# Drive_Board_Schematic_3_motors.net
KiCad netlist of a schematic drawn in Altium Designer
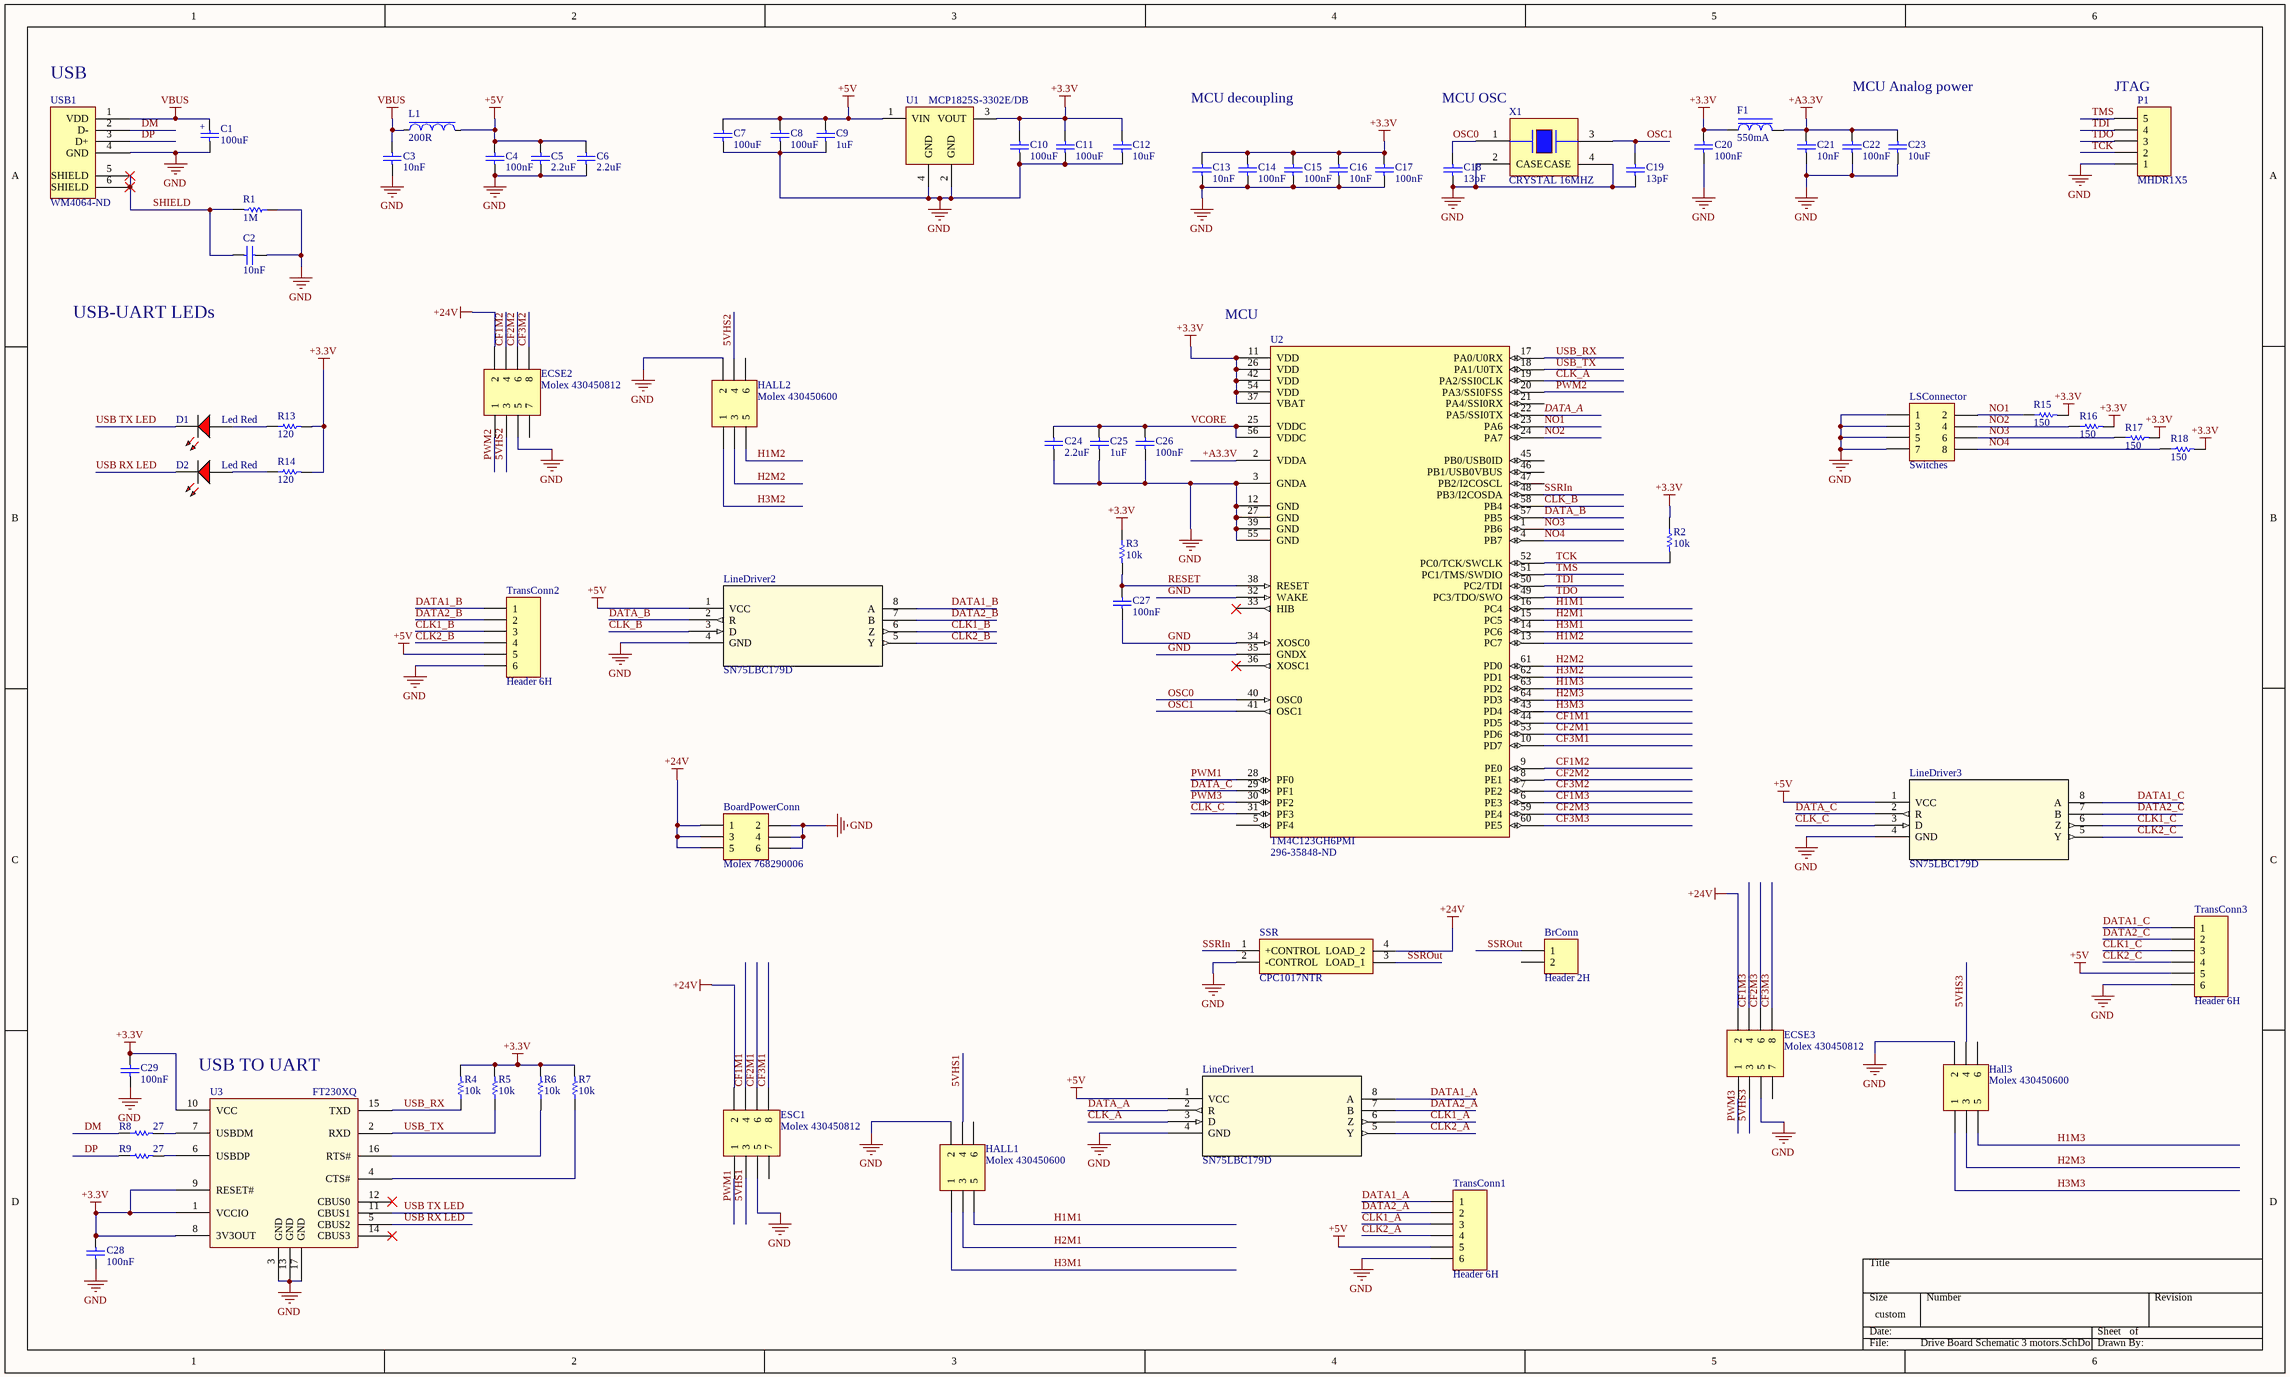
[diagram p0: Drive Board Schematic 3 motors.SchDoc]

(export (version "E")
  (design (tool "Eeschema 10.0.6"))
  (components
    (comp (ref "BoardPowerConn")
      (value "Molex 768290006")
      (footprint "HDR2X3H")
      (description "Header, 3-Pin, Dual row, Right Angle")
      (fields (field (name "PUBLISHER") "Altium Limited"))
      (libsource (lib "") (part "Header 3X2H_1"))
    )
    (comp (ref "BrConn")
      (value "Header 2H")
      (footprint "HDR1X2H")
      (description "Header, 2-Pin, Right Angle")
      (fields (field (name "PUBLISHER") "Altium Limited"))
      (libsource (lib "Miscellaneous Connectors") (part "Header 2H"))
    )
    (comp (ref "C1")
      (value "100uF")
      (footprint "CapAlu6.3mmx12.5mm")
      (description "Capacitor 35v 100uF 6.3mm")
      (fields
        (field (name "MANUFACTURER") "Nichicon")
        (field (name "MANUFACTURER PART NUMBER") "UHV1V101MED")
      )
      (libsource (lib "Capacitors") (part "100uF_35v_6.3x12.5"))
    )
    (comp (ref "C2")
      (value "10nF")
      (footprint "CAP_1206")
      (description "CAP CER 10000PF 500V X7R 1206")
      (fields
        (field (name "MANUFACTURER") "Samsung Electro-Mechanics America, Inc")
        (field (name "MANUFACTURER PART NUMBER") "CL31B103KGFNNNE")
      )
      (libsource (lib "Capacitors") (part "10nF_500V_1206"))
    )
    (comp (ref "C3")
      (value "10nF")
      (footprint "CAP_0402_M")
      (description "CAP CER 10000PF 50V 10% X7R 0402")
      (fields
        (field (name "MANUFACTURER") "Kemet")
        (field (name "MANUFACTURER PART NUMBER") "C0402C103K5RACTU")
      )
      (libsource (lib "Capacitors") (part "10nF_50V_0402"))
    )
    (comp (ref "C4")
      (value "100nF")
      (footprint "CAP_0402_M")
      (description "CAP CER 100NF 50V 20% X5R 0402")
      (fields
        (field (name "MANUFACTURER") "TDK Corporation")
        (field (name "MANUFACTURER PART NUMBER") "C1005X5R1H104M050BB")
      )
      (libsource (lib "Capacitors") (part "100nF_50V_0402"))
    )
    (comp (ref "C5")
      (value "2.2uF")
      (footprint "CAP_0402_M")
      (description "CAP CER 2.2UF 10V 20% X5R 0402")
      (fields
        (field (name "MANUFACTURER") "Taiyo Yuden")
        (field (name "MANUFACTURER PART NUMBER") "LMK105BJ225MV-F")
      )
      (libsource (lib "Capacitors") (part "2.2uF_10V_0402"))
    )
    (comp (ref "C6")
      (value "2.2uF")
      (footprint "CAP_0402_M")
      (description "CAP CER 2.2UF 10V 20% X5R 0402")
      (fields
        (field (name "MANUFACTURER") "Taiyo Yuden")
        (field (name "MANUFACTURER PART NUMBER") "LMK105BJ225MV-F")
      )
      (libsource (lib "Capacitors") (part "2.2uF_10V_0402"))
    )
    (comp (ref "C7")
      (value "100uF")
      (footprint "CAP_1206")
      (description "CAP CER 100UF 6.3V X5R 1206")
      (fields
        (field (name "MANUFACTURER") "Murata Electronics North America")
        (field (name "MANUFACTURER PART NUMBER") "GRM31CR60J107ME39L")
      )
      (libsource (lib "Capacitors") (part "100uF_6.3v_1206_X5R"))
    )
    (comp (ref "C8")
      (value "100uF")
      (footprint "CAP_1206")
      (description "CAP CER 100UF 6.3V X5R 1206")
      (fields
        (field (name "MANUFACTURER") "Murata Electronics North America")
        (field (name "MANUFACTURER PART NUMBER") "GRM31CR60J107ME39L")
      )
      (libsource (lib "Capacitors") (part "100uF_6.3v_1206_X5R"))
    )
    (comp (ref "C9")
      (value "1uF")
      (footprint "CAP_0402_M")
      (description "CAP CER 1UF 25V 10% X5R 0402")
      (fields
        (field (name "MANUFACTURER") "TDK Corporation")
        (field (name "MANUFACTURER PART NUMBER") "C1005X5R1E105K050BC")
      )
      (libsource (lib "Capacitors") (part "1uF_25V_0402"))
    )
    (comp (ref "C10")
      (value "100uF")
      (footprint "CAP_1206")
      (description "CAP CER 100UF 6.3V X5R 1206")
      (fields
        (field (name "MANUFACTURER") "Murata Electronics North America")
        (field (name "MANUFACTURER PART NUMBER") "GRM31CR60J107ME39L")
      )
      (libsource (lib "Capacitors") (part "100uF_6.3v_1206_X5R"))
    )
    (comp (ref "C11")
      (value "100uF")
      (footprint "CAP_1206")
      (description "CAP CER 100UF 6.3V X5R 1206")
      (fields
        (field (name "MANUFACTURER") "Murata Electronics North America")
        (field (name "MANUFACTURER PART NUMBER") "GRM31CR60J107ME39L")
      )
      (libsource (lib "Capacitors") (part "100uF_6.3v_1206_X5R"))
    )
    (comp (ref "C12")
      (value "10uF")
      (footprint "CAP_0603")
      (description "CAP CER 10UF 10V 20% X5R 0603")
      (fields
        (field (name "MANUFACTURER") "Taiyo Yuden")
        (field (name "MANUFACTURER PART NUMBER") "LMK107BBJ106MAHT")
      )
      (libsource (lib "Capacitors") (part "10uF_10V_0603"))
    )
    (comp (ref "C13")
      (value "10nF")
      (footprint "CAP_0402_M")
      (description "CAP CER 10000PF 50V 10% X7R 0402")
      (fields
        (field (name "MANUFACTURER") "Kemet")
        (field (name "MANUFACTURER PART NUMBER") "C0402C103K5RACTU")
      )
      (libsource (lib "Capacitors") (part "10nF_50V_0402"))
    )
    (comp (ref "C14")
      (value "100nF")
      (footprint "CAP_0402_M")
      (description "CAP CER 100NF 50V 20% X5R 0402")
      (fields
        (field (name "MANUFACTURER") "TDK Corporation")
        (field (name "MANUFACTURER PART NUMBER") "C1005X5R1H104M050BB")
      )
      (libsource (lib "Capacitors") (part "100nF_50V_0402"))
    )
    (comp (ref "C15")
      (value "100nF")
      (footprint "CAP_0402_M")
      (description "CAP CER 100NF 50V 20% X5R 0402")
      (fields
        (field (name "MANUFACTURER") "TDK Corporation")
        (field (name "MANUFACTURER PART NUMBER") "C1005X5R1H104M050BB")
      )
      (libsource (lib "Capacitors") (part "100nF_50V_0402"))
    )
    (comp (ref "C16")
      (value "10nF")
      (footprint "CAP_0402_M")
      (description "CAP CER 10000PF 50V 10% X7R 0402")
      (fields
        (field (name "MANUFACTURER") "Kemet")
        (field (name "MANUFACTURER PART NUMBER") "C0402C103K5RACTU")
      )
      (libsource (lib "Capacitors") (part "10nF_50V_0402"))
    )
    (comp (ref "C17")
      (value "100nF")
      (footprint "CAP_0402_M")
      (description "CAP CER 100NF 50V 20% X5R 0402")
      (fields
        (field (name "MANUFACTURER") "TDK Corporation")
        (field (name "MANUFACTURER PART NUMBER") "C1005X5R1H104M050BB")
      )
      (libsource (lib "Capacitors") (part "100nF_50V_0402"))
    )
    (comp (ref "C18")
      (value "13pF")
      (footprint "CAP_0402_M")
      (description "CAP CER 13PF 50V 5% NP0 0402")
      (fields
        (field (name "MANUFACTURER") "Samsung Electro-Mechanics America, Inc")
        (field (name "MANUFACTURER PART NUMBER") "CL05C130JB5NNNC")
      )
      (libsource (lib "Capacitors") (part "13pF_50V_0402"))
    )
    (comp (ref "C19")
      (value "13pF")
      (footprint "CAP_0402_M")
      (description "CAP CER 13PF 50V 5% NP0 0402")
      (fields
        (field (name "MANUFACTURER") "Samsung Electro-Mechanics America, Inc")
        (field (name "MANUFACTURER PART NUMBER") "CL05C130JB5NNNC")
      )
      (libsource (lib "Capacitors") (part "13pF_50V_0402"))
    )
    (comp (ref "C20")
      (value "100nF")
      (footprint "CAP_0402_M")
      (description "CAP CER 100NF 50V 20% X5R 0402")
      (fields
        (field (name "MANUFACTURER") "TDK Corporation")
        (field (name "MANUFACTURER PART NUMBER") "C1005X5R1H104M050BB")
      )
      (libsource (lib "Capacitors") (part "100nF_50V_0402"))
    )
    (comp (ref "C21")
      (value "10nF")
      (footprint "CAP_0402_M")
      (description "CAP CER 10000PF 50V 10% X7R 0402")
      (fields
        (field (name "MANUFACTURER") "Kemet")
        (field (name "MANUFACTURER PART NUMBER") "C0402C103K5RACTU")
      )
      (libsource (lib "Capacitors") (part "10nF_50V_0402"))
    )
    (comp (ref "C22")
      (value "100nF")
      (footprint "CAP_0402_M")
      (description "CAP CER 100NF 50V 20% X5R 0402")
      (fields
        (field (name "MANUFACTURER") "TDK Corporation")
        (field (name "MANUFACTURER PART NUMBER") "C1005X5R1H104M050BB")
      )
      (libsource (lib "Capacitors") (part "100nF_50V_0402"))
    )
    (comp (ref "C23")
      (value "10uF")
      (footprint "CAP_0603")
      (description "CAP CER 10UF 10V 20% X5R 0603")
      (fields
        (field (name "MANUFACTURER") "Taiyo Yuden")
        (field (name "MANUFACTURER PART NUMBER") "LMK107BBJ106MAHT")
      )
      (libsource (lib "Capacitors") (part "10uF_10V_0603"))
    )
    (comp (ref "C24")
      (value "2.2uF")
      (footprint "CAP_0603")
      (description "CAP CER 2.2UF 35V 10% X5R 0603")
      (fields
        (field (name "MANUFACTURER") "Murata Electronics North America")
        (field (name "MANUFACTURER PART NUMBER") "GRM188R6YA225KA12D")
      )
      (libsource (lib "Capacitors") (part "2.2uF_35V_0603"))
    )
    (comp (ref "C25")
      (value "1uF")
      (footprint "CAP_0402_M")
      (description "CAP CER 1UF 25V 10% X5R 0402")
      (fields
        (field (name "MANUFACTURER") "TDK Corporation")
        (field (name "MANUFACTURER PART NUMBER") "C1005X5R1E105K050BC")
      )
      (libsource (lib "Capacitors") (part "1uF_25V_0402"))
    )
    (comp (ref "C26")
      (value "100nF")
      (footprint "CAP_0402_M")
      (description "CAP CER 100NF 50V 20% X5R 0402")
      (fields
        (field (name "MANUFACTURER") "TDK Corporation")
        (field (name "MANUFACTURER PART NUMBER") "C1005X5R1H104M050BB")
      )
      (libsource (lib "Capacitors") (part "100nF_50V_0402"))
    )
    (comp (ref "C27")
      (value "100nF")
      (footprint "CAP_0402_M")
      (description "CAP CER 100NF 50V 20% X5R 0402")
      (fields
        (field (name "MANUFACTURER") "TDK Corporation")
        (field (name "MANUFACTURER PART NUMBER") "C1005X5R1H104M050BB")
      )
      (libsource (lib "Capacitors") (part "100nF_50V_0402"))
    )
    (comp (ref "C28")
      (value "100nF")
      (footprint "CAP_0402_M")
      (description "CAP CER 100NF 50V 20% X5R 0402")
      (fields
        (field (name "MANUFACTURER") "TDK Corporation")
        (field (name "MANUFACTURER PART NUMBER") "C1005X5R1H104M050BB")
      )
      (libsource (lib "Capacitors") (part "100nF_50V_0402"))
    )
    (comp (ref "C29")
      (value "100nF")
      (footprint "CAP_0402_M")
      (description "CAP CER 100NF 50V 20% X5R 0402")
      (fields
        (field (name "MANUFACTURER") "TDK Corporation")
        (field (name "MANUFACTURER PART NUMBER") "C1005X5R1H104M050BB")
      )
      (libsource (lib "Capacitors") (part "100nF_50V_0402"))
    )
    (comp (ref "D1")
      (value "Led Red")
      (footprint "TOPLED 0805")
      (description "LED TOPLED 630NM SUP RED CLR SMD")
      (fields
        (field (name "MANUFACTURER") "OSRAM Opto Semiconductors Inc")
        (field (name "MANUFACTURER PART NUMBER") "LS M67K-H2L1-1-Z")
      )
      (libsource (lib "Diodes") (part "TOPLED 0803"))
    )
    (comp (ref "D2")
      (value "Led Red")
      (footprint "TOPLED 0805")
      (description "LED TOPLED 630NM SUP RED CLR SMD")
      (fields
        (field (name "MANUFACTURER") "OSRAM Opto Semiconductors Inc")
        (field (name "MANUFACTURER PART NUMBER") "LS M67K-H2L1-1-Z")
      )
      (libsource (lib "Diodes") (part "TOPLED 0803"))
    )
    (comp (ref "ECSE2")
      (value "Molex 430450812")
      (footprint "HDR2X4H")
      (description "Header, 4-Pin, Dual row, Right Angle")
      (fields (field (name "PUBLISHER") "Altium Limited"))
      (libsource (lib "Miscellaneous Connectors") (part "Header 4X2H"))
    )
    (comp (ref "ECSE3")
      (value "Molex 430450812")
      (footprint "HDR2X4H")
      (description "Header, 4-Pin, Dual row, Right Angle")
      (fields (field (name "PUBLISHER") "Altium Limited"))
      (libsource (lib "Miscellaneous Connectors") (part "Header 4X2H"))
    )
    (comp (ref "ESC1")
      (value "Molex 430450812")
      (footprint "HDR2X4H")
      (description "Header, 4-Pin, Dual row, Right Angle")
      (fields (field (name "PUBLISHER") "Altium Limited"))
      (libsource (lib "Miscellaneous Connectors") (part "Header 4X2H"))
    )
    (comp (ref "F1")
      (value "550mA")
      (footprint "RES_0402_M")
      (description "FERRITE CHIP 40 OHM 550MA 0402")
      (fields
        (field (name "MANUFACTURER") "TDK Corporation")
        (field (name "MANUFACTURER PART NUMBER") "MMZ1005Y400CT000")
      )
      (libsource (lib "Resistors") (part "40O_550mA_0402"))
    )
    (comp (ref "HALL1")
      (value "Molex 430450600")
      (footprint "HDR2X3H")
      (description "Header, 3-Pin, Dual row, Right Angle")
      (fields (field (name "PUBLISHER") "Altium Limited"))
      (libsource (lib "Miscellaneous Connectors") (part "Header 3X2H"))
    )
    (comp (ref "HALL2")
      (value "Molex 430450600")
      (footprint "HDR2X3H")
      (description "Header, 3-Pin, Dual row, Right Angle")
      (fields (field (name "PUBLISHER") "Altium Limited"))
      (libsource (lib "Miscellaneous Connectors") (part "Header 3X2H"))
    )
    (comp (ref "Hall3")
      (value "Molex 430450600")
      (footprint "HDR2X3H")
      (description "Header, 3-Pin, Dual row, Right Angle")
      (fields (field (name "PUBLISHER") "Altium Limited"))
      (libsource (lib "Miscellaneous Connectors") (part "Header 3X2H"))
    )
    (comp (ref "L1")
      (value "200R")
      (footprint "IND_0603")
      (description "FILTER CHIP 220 OHM 2A 0603")
      (fields
        (field (name "MANUFACTURER") "Murata Electronics North America")
        (field (name "MANUFACTURER PART NUMBER") "BLM18EG221SN1D")
      )
      (libsource (lib "Inductors") (part "Ferrite_200 ohms_2A"))
    )
    (comp (ref "LineDriver1")
      (value "SN75LBC179D")
      (footprint "D8")
      (description "Low-Power Differential Line Driver And Receiver Pair")
      (fields
        (field (name "MANUFACTURER") "Texas Instruments")
        (field (name "GENERIC_PART_NUMBER") "SN75LBC179")
        (field (name "COPYRIGHT") "Copyright (C) 2018 Accelerated Designs. All rights reserved")
      )
      (libsource (lib "2020-08-25_19-06-54") (part "SN75LBC179D"))
    )
    (comp (ref "LineDriver2")
      (value "SN75LBC179D")
      (footprint "D8")
      (description "Low-Power Differential Line Driver And Receiver Pair")
      (fields
        (field (name "MANUFACTURER") "Texas Instruments")
        (field (name "GENERIC_PART_NUMBER") "SN75LBC179")
        (field (name "COPYRIGHT") "Copyright (C) 2018 Accelerated Designs. All rights reserved")
      )
      (libsource (lib "2020-08-25_19-06-54") (part "SN75LBC179D"))
    )
    (comp (ref "LineDriver3")
      (value "SN75LBC179D")
      (footprint "D8")
      (description "Low-Power Differential Line Driver And Receiver Pair")
      (fields
        (field (name "MANUFACTURER") "Texas Instruments")
        (field (name "GENERIC_PART_NUMBER") "SN75LBC179")
        (field (name "COPYRIGHT") "Copyright (C) 2018 Accelerated Designs. All rights reserved")
      )
      (libsource (lib "2020-08-25_19-06-54") (part "SN75LBC179D"))
    )
    (comp (ref "LSConnector")
      (value "Switches")
      (footprint "MHDR2X4")
      (description "Header, 4-Pin, Dual row")
      (fields (field (name "PUBLISHER") "Altium Limited"))
      (libsource (lib "Miscellaneous Connectors") (part "MHDR2X4"))
    )
    (comp (ref "P1")
      (value "MHDR1X5")
      (footprint "MHDR1X5")
      (description "Header, 5-Pin")
      (fields (field (name "PUBLISHER") "Altium Limited"))
      (libsource (lib "Miscellaneous Connectors") (part "MHDR1X5"))
    )
    (comp (ref "R1")
      (value "1M")
      (footprint "RES_1206")
      (description "RES SMD 1M OHM 5% 1/4W 1206")
      (fields
        (field (name "MANUFACTURER") "Panasonic Electronic Components")
        (field (name "MANUFACTURER PART NUMBER") "ERJ-8GEYJ105V")
      )
      (libsource (lib "Resistors") (part "1M_5%_1206"))
    )
    (comp (ref "R2")
      (value "10k")
      (footprint "RES_0402_M")
      (description "RES SMD 10K OHM 1% 1/10W 0402")
      (fields
        (field (name "MANUFACTURER") "Panasonic Electronic Components")
        (field (name "MANUFACTURER PART NUMBER") "ERJ-2RKF1002X")
      )
      (libsource (lib "Resistors") (part "10k_1%_0402"))
    )
    (comp (ref "R3")
      (value "10k")
      (footprint "RES_0402_M")
      (description "RES SMD 10K OHM 1% 1/10W 0402")
      (fields
        (field (name "MANUFACTURER") "Panasonic Electronic Components")
        (field (name "MANUFACTURER PART NUMBER") "ERJ-2RKF1002X")
      )
      (libsource (lib "Resistors") (part "10k_1%_0402"))
    )
    (comp (ref "R4")
      (value "10k")
      (footprint "RES_0402_M")
      (description "RES SMD 10K OHM 1% 1/10W 0402")
      (fields
        (field (name "MANUFACTURER") "Panasonic Electronic Components")
        (field (name "MANUFACTURER PART NUMBER") "ERJ-2RKF1002X")
      )
      (libsource (lib "Resistors") (part "10k_1%_0402"))
    )
    (comp (ref "R5")
      (value "10k")
      (footprint "RES_0402_M")
      (description "RES SMD 10K OHM 1% 1/10W 0402")
      (fields
        (field (name "MANUFACTURER") "Panasonic Electronic Components")
        (field (name "MANUFACTURER PART NUMBER") "ERJ-2RKF1002X")
      )
      (libsource (lib "Resistors") (part "10k_1%_0402"))
    )
    (comp (ref "R6")
      (value "10k")
      (footprint "RES_0402_M")
      (description "RES SMD 10K OHM 1% 1/10W 0402")
      (fields
        (field (name "MANUFACTURER") "Panasonic Electronic Components")
        (field (name "MANUFACTURER PART NUMBER") "ERJ-2RKF1002X")
      )
      (libsource (lib "Resistors") (part "10k_1%_0402"))
    )
    (comp (ref "R7")
      (value "10k")
      (footprint "RES_0402_M")
      (description "RES SMD 10K OHM 1% 1/10W 0402")
      (fields
        (field (name "MANUFACTURER") "Panasonic Electronic Components")
        (field (name "MANUFACTURER PART NUMBER") "ERJ-2RKF1002X")
      )
      (libsource (lib "Resistors") (part "10k_1%_0402"))
    )
    (comp (ref "R8")
      (value "27")
      (footprint "RES_0402_M")
      (description "RES SMD 27 OHM 1% 1/10W 0402")
      (fields
        (field (name "MANUFACTURER") "Panasonic Electronic Components")
        (field (name "MANUFACTURER PART NUMBER") "ERJ-2RKF27R0X")
      )
      (libsource (lib "Resistors") (part "27_1%_0402"))
    )
    (comp (ref "R9")
      (value "27")
      (footprint "RES_0402_M")
      (description "RES SMD 27 OHM 1% 1/10W 0402")
      (fields
        (field (name "MANUFACTURER") "Panasonic Electronic Components")
        (field (name "MANUFACTURER PART NUMBER") "ERJ-2RKF27R0X")
      )
      (libsource (lib "Resistors") (part "27_1%_0402"))
    )
    (comp (ref "R13")
      (value "120")
      (footprint "RES_0402_M")
      (description "RES SMD 120 OHM 1% 1/10W 0402")
      (fields
        (field (name "MANUFACTURER") "Panasonic Electronic Components")
        (field (name "MANUFACTURER PART NUMBER") "ERJ-2RKF1200X")
      )
      (libsource (lib "Resistors") (part "120_1%_0402"))
    )
    (comp (ref "R14")
      (value "120")
      (footprint "RES_0402_M")
      (description "RES SMD 120 OHM 1% 1/10W 0402")
      (fields
        (field (name "MANUFACTURER") "Panasonic Electronic Components")
        (field (name "MANUFACTURER PART NUMBER") "ERJ-2RKF1200X")
      )
      (libsource (lib "Resistors") (part "120_1%_0402"))
    )
    (comp (ref "R15")
      (value "150")
      (footprint "RES_0402_M")
      (description "RES SMD 10K OHM 1% 1/10W 0402")
      (fields
        (field (name "MANUFACTURER") "Panasonic Electronic Components")
        (field (name "MANUFACTURER PART NUMBER") "ERJ-2RKF1002X")
      )
      (libsource (lib "Resistors") (part "10k_1%_0402"))
    )
    (comp (ref "R16")
      (value "150")
      (footprint "RES_0402_M")
      (description "RES SMD 10K OHM 1% 1/10W 0402")
      (fields
        (field (name "MANUFACTURER") "Panasonic Electronic Components")
        (field (name "MANUFACTURER PART NUMBER") "ERJ-2RKF1002X")
      )
      (libsource (lib "Resistors") (part "10k_1%_0402"))
    )
    (comp (ref "R17")
      (value "150")
      (footprint "RES_0402_M")
      (description "RES SMD 10K OHM 1% 1/10W 0402")
      (fields
        (field (name "MANUFACTURER") "Panasonic Electronic Components")
        (field (name "MANUFACTURER PART NUMBER") "ERJ-2RKF1002X")
      )
      (libsource (lib "Resistors") (part "10k_1%_0402"))
    )
    (comp (ref "R18")
      (value "150")
      (footprint "RES_0402_M")
      (description "RES SMD 10K OHM 1% 1/10W 0402")
      (fields
        (field (name "MANUFACTURER") "Panasonic Electronic Components")
        (field (name "MANUFACTURER PART NUMBER") "ERJ-2RKF1002X")
      )
      (libsource (lib "Resistors") (part "10k_1%_0402"))
    )
    (comp (ref "SSR")
      (value "CPC1017NTR")
      (footprint "SamacSys:SOP254P610X216-4N")
      (description "Relay or Contactor")
      (fields (field (name "MOUSER PART NUMBER") "849-CPC1017NTR"))
      (libsource (lib "*") (part "CPC1017NTR"))
    )
    (comp (ref "TransConn1")
      (value "Header 6H")
      (footprint "HDR1X6H")
      (description "Header, 6-Pin, Right Angle")
      (fields (field (name "PUBLISHER") "Altium Limited"))
      (libsource (lib "Miscellaneous Connectors") (part "Header 6H"))
    )
    (comp (ref "TransConn2")
      (value "Header 6H")
      (footprint "HDR1X6H")
      (description "Header, 6-Pin, Right Angle")
      (fields (field (name "PUBLISHER") "Altium Limited"))
      (libsource (lib "Miscellaneous Connectors") (part "Header 6H"))
    )
    (comp (ref "TransConn3")
      (value "Header 6H")
      (footprint "HDR1X6H")
      (description "Header, 6-Pin, Right Angle")
      (fields (field (name "PUBLISHER") "Altium Limited"))
      (libsource (lib "Miscellaneous Connectors") (part "Header 6H"))
    )
    (comp (ref "U1")
      (value "MCP1825S-3302E/DB")
      (footprint "SOT230P700X180-4N")
      (description "500 mA, Low Voltage, Low Quiescent Current LDO Regulator")
      (fields (field (name "MANUFACTURER") "Microchip Technology"))
      (libsource (lib "ICs") (part "MCP1825S-3302E/DB"))
    )
    (comp (ref "U2")
      (value "TM4C123GH6PMI")
      (footprint "TSQFP50P1200X1200X120-64N")
      (description "Tiva TM4C123GH6PM Microcontroller ARM Cortex 80 MHz FPU")
      (fields (field (name "SUPPLIER PART NUMBER 1") "296-35848-ND"))
      (libsource (lib "ICs") (part "TM4C123GH6PMI"))
    )
    (comp (ref "U3")
      (value "FT230XQ")
      (footprint "QFN65P400X400X80_HS-17N")
      (description "IC USB SERIAL BASIC UART 16QFN")
      (fields
        (field (name "MANUFACTURER") "FTDI, Future Technology Devices International Ltd")
        (field (name "MANUFACTURER PART NUMBER") "FT230XQ-R")
      )
      (libsource (lib "ICs") (part "FT230XQ-R"))
    )
    (comp (ref "USB1")
      (value "USB type-B jack")
      (footprint "USB2.5-2H4E")
      (fields (field (name "SUPPLIER PART NUMBER 1") "WM4064-ND"))
      (libsource (lib "Connectors") (part "MOLEX 0670688010"))
    )
    (comp (ref "X1")
      (value "CRYSTAL 16MHZ")
      (footprint "CRYSTAL_3.2x2.5")
      (description "CRYSTAL 16MHZ 20PF SMD")
      (fields
        (field (name "MANUFACTURER") "CTS-Frequency Controls")
        (field (name "MANUFACTURER PART NUMBER") "403C35E16M00000")
      )
      (libsource (lib "ICs") (part "403C35E16M00000"))
    )
  )
  (nets
    (net (code "1") (name "+3.3V") (class "Default")
      (node (ref "C10") (pin "1") (pinfunction "1_1") (pintype "passive"))
      (node (ref "C11") (pin "1") (pinfunction "1_1") (pintype "passive"))
      (node (ref "C12") (pin "1") (pinfunction "1_1") (pintype "passive"))
      (node (ref "C13") (pin "2") (pinfunction "2_2") (pintype "passive"))
      (node (ref "C14") (pin "2") (pinfunction "2_2") (pintype "passive"))
      (node (ref "C15") (pin "2") (pinfunction "2_2") (pintype "passive"))
      (node (ref "C16") (pin "2") (pinfunction "2_2") (pintype "passive"))
      (node (ref "C17") (pin "2") (pinfunction "2_2") (pintype "passive"))
      (node (ref "C20") (pin "2") (pinfunction "2_2") (pintype "passive"))
      (node (ref "C28") (pin "2") (pinfunction "2_2") (pintype "passive"))
      (node (ref "C29") (pin "2") (pinfunction "2_2") (pintype "passive"))
      (node (ref "F1") (pin "1") (pinfunction "1_1") (pintype "passive"))
      (node (ref "R13") (pin "2") (pinfunction "2_2") (pintype "passive"))
      (node (ref "R14") (pin "2") (pinfunction "2_2") (pintype "passive"))
      (node (ref "R15") (pin "2") (pinfunction "2_2") (pintype "passive"))
      (node (ref "R16") (pin "2") (pinfunction "2_2") (pintype "passive"))
      (node (ref "R17") (pin "2") (pinfunction "2_2") (pintype "passive"))
      (node (ref "R18") (pin "2") (pinfunction "2_2") (pintype "passive"))
      (node (ref "R2") (pin "1") (pinfunction "1_1") (pintype "passive"))
      (node (ref "R3") (pin "1") (pinfunction "1_1") (pintype "passive"))
      (node (ref "R4") (pin "2") (pinfunction "2_2") (pintype "passive"))
      (node (ref "R5") (pin "2") (pinfunction "2_2") (pintype "passive"))
      (node (ref "R6") (pin "2") (pinfunction "2_2") (pintype "passive"))
      (node (ref "R7") (pin "2") (pinfunction "2_2") (pintype "passive"))
      (node (ref "U1") (pin "3") (pinfunction "VOUT_3") (pintype "power_in"))
      (node (ref "U2") (pin "11") (pinfunction "VDD_11") (pintype "power_in"))
      (node (ref "U2") (pin "26") (pinfunction "VDD_26") (pintype "power_in"))
      (node (ref "U2") (pin "37") (pinfunction "VBAT_37") (pintype "power_in"))
      (node (ref "U2") (pin "42") (pinfunction "VDD_42") (pintype "power_in"))
      (node (ref "U2") (pin "54") (pinfunction "VDD_54") (pintype "power_in"))
      (node (ref "U3") (pin "1") (pinfunction "VCCIO_1") (pintype "passive"))
      (node (ref "U3") (pin "10") (pinfunction "VCC_10") (pintype "passive"))
      (node (ref "U3") (pin "8") (pinfunction "3V3OUT_8") (pintype "passive"))
      (node (ref "U3") (pin "9") (pinfunction "RESET#_9") (pintype "passive"))
    )
    (net (code "2") (name "+5V") (class "Default")
      (node (ref "C4") (pin "2") (pinfunction "2_2") (pintype "passive"))
      (node (ref "C5") (pin "2") (pinfunction "2_2") (pintype "passive"))
      (node (ref "C6") (pin "2") (pinfunction "2_2") (pintype "passive"))
      (node (ref "C7") (pin "1") (pinfunction "1_1") (pintype "passive"))
      (node (ref "C8") (pin "1") (pinfunction "1_1") (pintype "passive"))
      (node (ref "C9") (pin "2") (pinfunction "2_2") (pintype "passive"))
      (node (ref "L1") (pin "2") (pinfunction "2_2") (pintype "passive"))
      (node (ref "LineDriver1") (pin "1") (pinfunction "VCC_1") (pintype "power_in"))
      (node (ref "LineDriver2") (pin "1") (pinfunction "VCC_1") (pintype "power_in"))
      (node (ref "LineDriver3") (pin "1") (pinfunction "VCC_1") (pintype "power_in"))
      (node (ref "TransConn1") (pin "5") (pinfunction "5_5") (pintype "passive"))
      (node (ref "TransConn2") (pin "5") (pinfunction "5_5") (pintype "passive"))
      (node (ref "TransConn3") (pin "5") (pinfunction "5_5") (pintype "passive"))
      (node (ref "U1") (pin "1") (pinfunction "VIN_1") (pintype "power_in"))
    )
    (net (code "3") (name "+24V") (class "Default")
      (node (ref "BoardPowerConn") (pin "1") (pinfunction "1_1") (pintype "passive"))
      (node (ref "BoardPowerConn") (pin "3") (pinfunction "3_3") (pintype "passive"))
      (node (ref "BoardPowerConn") (pin "5") (pinfunction "5_5") (pintype "passive"))
      (node (ref "ECSE2") (pin "2") (pinfunction "2_2") (pintype "passive"))
      (node (ref "ECSE3") (pin "2") (pinfunction "2_2") (pintype "passive"))
      (node (ref "ESC1") (pin "2") (pinfunction "2_2") (pintype "passive"))
      (node (ref "SSR") (pin "4") (pinfunction "LOAD_2_4") (pintype "passive"))
    )
    (net (code "4") (name "+A3.3V") (class "Default")
      (node (ref "C21") (pin "2") (pinfunction "2_2") (pintype "passive"))
      (node (ref "C22") (pin "2") (pinfunction "2_2") (pintype "passive"))
      (node (ref "C23") (pin "2") (pinfunction "2_2") (pintype "passive"))
      (node (ref "F1") (pin "2") (pinfunction "2_2") (pintype "passive"))
      (node (ref "U2") (pin "2") (pinfunction "VDDA_2") (pintype "power_in"))
    )
    (net (code "5") (name "/5VHS1") (class "Default")
      (node (ref "ESC1") (pin "3") (pinfunction "3_3") (pintype "passive"))
      (node (ref "HALL1") (pin "4") (pinfunction "4_4") (pintype "passive"))
    )
    (net (code "6") (name "/5VHS2") (class "Default")
      (node (ref "ECSE2") (pin "3") (pinfunction "3_3") (pintype "passive"))
      (node (ref "HALL2") (pin "4") (pinfunction "4_4") (pintype "passive"))
    )
    (net (code "7") (name "/5VHS3") (class "Default")
      (node (ref "ECSE3") (pin "3") (pinfunction "3_3") (pintype "passive"))
      (node (ref "Hall3") (pin "4") (pinfunction "4_4") (pintype "passive"))
    )
    (net (code "8") (name "/CF1M1") (class "Default")
      (node (ref "ESC1") (pin "4") (pinfunction "4_4") (pintype "passive"))
      (node (ref "U2") (pin "44") (pinfunction "PD5_44") (pintype "bidirectional"))
    )
    (net (code "9") (name "/CF1M2") (class "Default")
      (node (ref "ECSE2") (pin "4") (pinfunction "4_4") (pintype "passive"))
      (node (ref "U2") (pin "9") (pinfunction "PE0_9") (pintype "bidirectional"))
    )
    (net (code "10") (name "/CF1M3") (class "Default")
      (node (ref "ECSE3") (pin "4") (pinfunction "4_4") (pintype "passive"))
      (node (ref "U2") (pin "6") (pinfunction "PE3_6") (pintype "bidirectional"))
    )
    (net (code "11") (name "/CF2M1") (class "Default")
      (node (ref "ESC1") (pin "6") (pinfunction "6_6") (pintype "passive"))
      (node (ref "U2") (pin "53") (pinfunction "PD6_53") (pintype "bidirectional"))
    )
    (net (code "12") (name "/CF2M2") (class "Default")
      (node (ref "ECSE2") (pin "6") (pinfunction "6_6") (pintype "passive"))
      (node (ref "U2") (pin "8") (pinfunction "PE1_8") (pintype "bidirectional"))
    )
    (net (code "13") (name "/CF2M3") (class "Default")
      (node (ref "ECSE3") (pin "6") (pinfunction "6_6") (pintype "passive"))
      (node (ref "U2") (pin "59") (pinfunction "PE4_59") (pintype "bidirectional"))
    )
    (net (code "14") (name "/CF3M1") (class "Default")
      (node (ref "ESC1") (pin "8") (pinfunction "8_8") (pintype "passive"))
      (node (ref "U2") (pin "10") (pinfunction "PD7_10") (pintype "bidirectional"))
    )
    (net (code "15") (name "/CF3M2") (class "Default")
      (node (ref "ECSE2") (pin "8") (pinfunction "8_8") (pintype "passive"))
      (node (ref "U2") (pin "7") (pinfunction "PE2_7") (pintype "bidirectional"))
    )
    (net (code "16") (name "/CF3M3") (class "Default")
      (node (ref "ECSE3") (pin "8") (pinfunction "8_8") (pintype "passive"))
      (node (ref "U2") (pin "60") (pinfunction "PE5_60") (pintype "bidirectional"))
    )
    (net (code "17") (name "/CLK1_A") (class "Default")
      (node (ref "LineDriver1") (pin "6") (pinfunction "Z_6") (pintype "output"))
      (node (ref "TransConn1") (pin "3") (pinfunction "3_3") (pintype "passive"))
    )
    (net (code "18") (name "/CLK1_B") (class "Default")
      (node (ref "LineDriver2") (pin "6") (pinfunction "Z_6") (pintype "output"))
      (node (ref "TransConn2") (pin "3") (pinfunction "3_3") (pintype "passive"))
    )
    (net (code "19") (name "/CLK1_C") (class "Default")
      (node (ref "LineDriver3") (pin "6") (pinfunction "Z_6") (pintype "output"))
      (node (ref "TransConn3") (pin "3") (pinfunction "3_3") (pintype "passive"))
    )
    (net (code "20") (name "/CLK2_A") (class "Default")
      (node (ref "LineDriver1") (pin "5") (pinfunction "Y_5") (pintype "output"))
      (node (ref "TransConn1") (pin "4") (pinfunction "4_4") (pintype "passive"))
    )
    (net (code "21") (name "/CLK2_B") (class "Default")
      (node (ref "LineDriver2") (pin "5") (pinfunction "Y_5") (pintype "output"))
      (node (ref "TransConn2") (pin "4") (pinfunction "4_4") (pintype "passive"))
    )
    (net (code "22") (name "/CLK2_C") (class "Default")
      (node (ref "LineDriver3") (pin "5") (pinfunction "Y_5") (pintype "output"))
      (node (ref "TransConn3") (pin "4") (pinfunction "4_4") (pintype "passive"))
    )
    (net (code "23") (name "/CLK_A") (class "Default")
      (node (ref "LineDriver1") (pin "3") (pinfunction "D_3") (pintype "input"))
      (node (ref "U2") (pin "19") (pinfunction "PA2/SSI0CLK_19") (pintype "bidirectional"))
    )
    (net (code "24") (name "/CLK_B") (class "Default")
      (node (ref "LineDriver2") (pin "3") (pinfunction "D_3") (pintype "input"))
      (node (ref "U2") (pin "58") (pinfunction "PB4_58") (pintype "bidirectional"))
    )
    (net (code "25") (name "/CLK_C") (class "Default")
      (node (ref "LineDriver3") (pin "3") (pinfunction "D_3") (pintype "input"))
      (node (ref "U2") (pin "31") (pinfunction "PF3_31") (pintype "bidirectional"))
    )
    (net (code "26") (name "/DATA1_A") (class "Default")
      (node (ref "LineDriver1") (pin "8") (pinfunction "A_8") (pintype "passive"))
      (node (ref "TransConn1") (pin "1") (pinfunction "1_1") (pintype "passive"))
    )
    (net (code "27") (name "/DATA1_B") (class "Default")
      (node (ref "LineDriver2") (pin "8") (pinfunction "A_8") (pintype "passive"))
      (node (ref "TransConn2") (pin "1") (pinfunction "1_1") (pintype "passive"))
    )
    (net (code "28") (name "/DATA1_C") (class "Default")
      (node (ref "LineDriver3") (pin "8") (pinfunction "A_8") (pintype "passive"))
      (node (ref "TransConn3") (pin "1") (pinfunction "1_1") (pintype "passive"))
    )
    (net (code "29") (name "/DATA2_A") (class "Default")
      (node (ref "LineDriver1") (pin "7") (pinfunction "B_7") (pintype "passive"))
      (node (ref "TransConn1") (pin "2") (pinfunction "2_2") (pintype "passive"))
    )
    (net (code "30") (name "/DATA2_B") (class "Default")
      (node (ref "LineDriver2") (pin "7") (pinfunction "B_7") (pintype "passive"))
      (node (ref "TransConn2") (pin "2") (pinfunction "2_2") (pintype "passive"))
    )
    (net (code "31") (name "/DATA2_C") (class "Default")
      (node (ref "LineDriver3") (pin "7") (pinfunction "B_7") (pintype "passive"))
      (node (ref "TransConn3") (pin "2") (pinfunction "2_2") (pintype "passive"))
    )
    (net (code "32") (name "/DATA_A") (class "Default")
      (node (ref "LineDriver1") (pin "2") (pinfunction "R_2") (pintype "output"))
      (node (ref "U2") (pin "22") (pinfunction "PA5/SSI0TX_22") (pintype "bidirectional"))
    )
    (net (code "33") (name "/DATA_B") (class "Default")
      (node (ref "LineDriver2") (pin "2") (pinfunction "R_2") (pintype "output"))
      (node (ref "U2") (pin "57") (pinfunction "PB5_57") (pintype "bidirectional"))
    )
    (net (code "34") (name "/DATA_C") (class "Default")
      (node (ref "LineDriver3") (pin "2") (pinfunction "R_2") (pintype "output"))
      (node (ref "U2") (pin "29") (pinfunction "PF1_29") (pintype "bidirectional"))
    )
    (net (code "35") (name "/DM") (class "Default")
      (node (ref "R8") (pin "1") (pinfunction "1_1") (pintype "passive"))
      (node (ref "USB1") (pin "2") (pinfunction "D-_2") (pintype "passive"))
    )
    (net (code "36") (name "/DP") (class "Default")
      (node (ref "R9") (pin "1") (pinfunction "1_1") (pintype "passive"))
      (node (ref "USB1") (pin "3") (pinfunction "D+_3") (pintype "passive"))
    )
    (net (code "37") (name "/H1M1") (class "Default")
      (node (ref "HALL1") (pin "5") (pinfunction "5_5") (pintype "passive"))
      (node (ref "U2") (pin "16") (pinfunction "PC4_16") (pintype "bidirectional"))
    )
    (net (code "38") (name "/H1M2") (class "Default")
      (node (ref "HALL2") (pin "5") (pinfunction "5_5") (pintype "passive"))
      (node (ref "U2") (pin "13") (pinfunction "PC7_13") (pintype "bidirectional"))
    )
    (net (code "39") (name "/H1M3") (class "Default")
      (node (ref "Hall3") (pin "5") (pinfunction "5_5") (pintype "passive"))
      (node (ref "U2") (pin "63") (pinfunction "PD2_63") (pintype "bidirectional"))
    )
    (net (code "40") (name "/H2M1") (class "Default")
      (node (ref "HALL1") (pin "3") (pinfunction "3_3") (pintype "passive"))
      (node (ref "U2") (pin "15") (pinfunction "PC5_15") (pintype "bidirectional"))
    )
    (net (code "41") (name "/H2M2") (class "Default")
      (node (ref "HALL2") (pin "3") (pinfunction "3_3") (pintype "passive"))
      (node (ref "U2") (pin "61") (pinfunction "PD0_61") (pintype "bidirectional"))
    )
    (net (code "42") (name "/H2M3") (class "Default")
      (node (ref "Hall3") (pin "3") (pinfunction "3_3") (pintype "passive"))
      (node (ref "U2") (pin "64") (pinfunction "PD3_64") (pintype "bidirectional"))
    )
    (net (code "43") (name "/H3M1") (class "Default")
      (node (ref "HALL1") (pin "1") (pinfunction "1_1") (pintype "passive"))
      (node (ref "U2") (pin "14") (pinfunction "PC6_14") (pintype "bidirectional"))
    )
    (net (code "44") (name "/H3M2") (class "Default")
      (node (ref "HALL2") (pin "1") (pinfunction "1_1") (pintype "passive"))
      (node (ref "U2") (pin "62") (pinfunction "PD1_62") (pintype "bidirectional"))
    )
    (net (code "45") (name "/H3M3") (class "Default")
      (node (ref "Hall3") (pin "1") (pinfunction "1_1") (pintype "passive"))
      (node (ref "U2") (pin "43") (pinfunction "PD4_43") (pintype "bidirectional"))
    )
    (net (code "46") (name "/NO1") (class "Default")
      (node (ref "LSConnector") (pin "2") (pinfunction "2_2") (pintype "passive"))
      (node (ref "R15") (pin "1") (pinfunction "1_1") (pintype "passive"))
      (node (ref "U2") (pin "23") (pinfunction "PA6_23") (pintype "bidirectional"))
    )
    (net (code "47") (name "/NO2") (class "Default")
      (node (ref "LSConnector") (pin "4") (pinfunction "4_4") (pintype "passive"))
      (node (ref "R16") (pin "1") (pinfunction "1_1") (pintype "passive"))
      (node (ref "U2") (pin "24") (pinfunction "PA7_24") (pintype "bidirectional"))
    )
    (net (code "48") (name "/NO3") (class "Default")
      (node (ref "LSConnector") (pin "6") (pinfunction "6_6") (pintype "passive"))
      (node (ref "R17") (pin "1") (pinfunction "1_1") (pintype "passive"))
      (node (ref "U2") (pin "1") (pinfunction "PB6_1") (pintype "bidirectional"))
    )
    (net (code "49") (name "/NO4") (class "Default")
      (node (ref "LSConnector") (pin "8") (pinfunction "8_8") (pintype "passive"))
      (node (ref "R18") (pin "1") (pinfunction "1_1") (pintype "passive"))
      (node (ref "U2") (pin "4") (pinfunction "PB7_4") (pintype "bidirectional"))
    )
    (net (code "50") (name "/OSC0") (class "Default")
      (node (ref "C18") (pin "2") (pinfunction "2_2") (pintype "passive"))
      (node (ref "U2") (pin "40") (pinfunction "OSC0_40") (pintype "input"))
      (node (ref "X1") (pin "1") (pintype "passive"))
    )
    (net (code "51") (name "/OSC1") (class "Default")
      (node (ref "C19") (pin "2") (pinfunction "2_2") (pintype "passive"))
      (node (ref "U2") (pin "41") (pinfunction "OSC1_41") (pintype "output"))
      (node (ref "X1") (pin "3") (pintype "passive"))
    )
    (net (code "52") (name "/PWM1") (class "Default")
      (node (ref "ESC1") (pin "1") (pinfunction "1_1") (pintype "passive"))
      (node (ref "U2") (pin "28") (pinfunction "PF0_28") (pintype "bidirectional"))
    )
    (net (code "53") (name "/PWM2") (class "Default")
      (node (ref "ECSE2") (pin "1") (pinfunction "1_1") (pintype "passive"))
      (node (ref "U2") (pin "20") (pinfunction "PA3/SSI0FSS_20") (pintype "bidirectional"))
    )
    (net (code "54") (name "/PWM3") (class "Default")
      (node (ref "ECSE3") (pin "1") (pinfunction "1_1") (pintype "passive"))
      (node (ref "U2") (pin "30") (pinfunction "PF2_30") (pintype "bidirectional"))
    )
    (net (code "55") (name "/RESET") (class "Default")
      (node (ref "C27") (pin "2") (pinfunction "2_2") (pintype "passive"))
      (node (ref "R3") (pin "2") (pinfunction "2_2") (pintype "passive"))
      (node (ref "U2") (pin "38") (pinfunction "RESET_38") (pintype "input"))
    )
    (net (code "56") (name "/SHIELD") (class "Default")
      (node (ref "C2") (pin "2") (pinfunction "2_2") (pintype "passive"))
      (node (ref "R1") (pin "2") (pinfunction "2_2") (pintype "passive"))
      (node (ref "USB1") (pin "5") (pinfunction "SHIELD_5") (pintype "passive"))
      (node (ref "USB1") (pin "6") (pinfunction "SHIELD_6") (pintype "passive"))
    )
    (net (code "57") (name "/SSRIn") (class "Default")
      (node (ref "SSR") (pin "1") (pinfunction "+CONTROL_1") (pintype "passive"))
      (node (ref "U2") (pin "48") (pinfunction "PB3/I2COSDA_48") (pintype "bidirectional"))
    )
    (net (code "58") (name "/SSROut") (class "Default")
      (node (ref "BrConn") (pin "1") (pinfunction "1_1") (pintype "passive"))
      (node (ref "SSR") (pin "3") (pinfunction "LOAD_1_3") (pintype "passive"))
    )
    (net (code "59") (name "/TCK") (class "Default")
      (node (ref "P1") (pin "2") (pinfunction "2_2") (pintype "passive"))
      (node (ref "R2") (pin "2") (pinfunction "2_2") (pintype "passive"))
      (node (ref "U2") (pin "52") (pinfunction "PC0/TCK/SWCLK_52") (pintype "bidirectional"))
    )
    (net (code "60") (name "/TDI") (class "Default")
      (node (ref "P1") (pin "4") (pinfunction "4_4") (pintype "passive"))
      (node (ref "U2") (pin "50") (pinfunction "PC2/TDI_50") (pintype "bidirectional"))
    )
    (net (code "61") (name "/TDO") (class "Default")
      (node (ref "P1") (pin "3") (pinfunction "3_3") (pintype "passive"))
      (node (ref "U2") (pin "49") (pinfunction "PC3/TDO/SWO_49") (pintype "bidirectional"))
    )
    (net (code "62") (name "/TMS") (class "Default")
      (node (ref "P1") (pin "5") (pinfunction "5_5") (pintype "passive"))
      (node (ref "U2") (pin "51") (pinfunction "PC1/TMS/SWDIO_51") (pintype "bidirectional"))
    )
    (net (code "63") (name "/USB RX LED") (class "Default")
      (node (ref "D2") (pin "2") (pinfunction "K_2") (pintype "passive"))
      (node (ref "U3") (pin "5") (pinfunction "CBUS2_5") (pintype "passive"))
    )
    (net (code "64") (name "/USB TX LED") (class "Default")
      (node (ref "D1") (pin "2") (pinfunction "K_2") (pintype "passive"))
      (node (ref "U3") (pin "11") (pinfunction "CBUS1_11") (pintype "passive"))
    )
    (net (code "65") (name "/USB_RX") (class "Default")
      (node (ref "R4") (pin "1") (pinfunction "1_1") (pintype "passive"))
      (node (ref "U2") (pin "17") (pinfunction "PA0/U0RX_17") (pintype "bidirectional"))
      (node (ref "U3") (pin "15") (pinfunction "TXD_15") (pintype "passive"))
    )
    (net (code "66") (name "/USB_TX") (class "Default")
      (node (ref "R5") (pin "1") (pinfunction "1_1") (pintype "passive"))
      (node (ref "U2") (pin "18") (pinfunction "PA1/U0TX_18") (pintype "bidirectional"))
      (node (ref "U3") (pin "2") (pinfunction "RXD_2") (pintype "passive"))
    )
    (net (code "67") (name "/VCORE") (class "Default")
      (node (ref "C24") (pin "2") (pinfunction "2_2") (pintype "passive"))
      (node (ref "C25") (pin "2") (pinfunction "2_2") (pintype "passive"))
      (node (ref "C26") (pin "2") (pinfunction "2_2") (pintype "passive"))
      (node (ref "U2") (pin "25") (pinfunction "VDDC_25") (pintype "power_in"))
      (node (ref "U2") (pin "56") (pinfunction "VDDC_56") (pintype "power_in"))
    )
    (net (code "68") (name "GND") (class "Default")
      (node (ref "BoardPowerConn") (pin "2") (pinfunction "2_2") (pintype "passive"))
      (node (ref "BoardPowerConn") (pin "4") (pinfunction "4_4") (pintype "passive"))
      (node (ref "BoardPowerConn") (pin "6") (pinfunction "6_6") (pintype "passive"))
      (node (ref "C1") (pin "2") (pinfunction "2_2") (pintype "passive"))
      (node (ref "C10") (pin "2") (pinfunction "2_2") (pintype "passive"))
      (node (ref "C11") (pin "2") (pinfunction "2_2") (pintype "passive"))
      (node (ref "C12") (pin "2") (pinfunction "2_2") (pintype "passive"))
      (node (ref "C13") (pin "1") (pinfunction "1_1") (pintype "passive"))
      (node (ref "C14") (pin "1") (pinfunction "1_1") (pintype "passive"))
      (node (ref "C15") (pin "1") (pinfunction "1_1") (pintype "passive"))
      (node (ref "C16") (pin "1") (pinfunction "1_1") (pintype "passive"))
      (node (ref "C17") (pin "1") (pinfunction "1_1") (pintype "passive"))
      (node (ref "C18") (pin "1") (pinfunction "1_1") (pintype "passive"))
      (node (ref "C19") (pin "1") (pinfunction "1_1") (pintype "passive"))
      (node (ref "C2") (pin "1") (pinfunction "1_1") (pintype "passive"))
      (node (ref "C20") (pin "1") (pinfunction "1_1") (pintype "passive"))
      (node (ref "C21") (pin "1") (pinfunction "1_1") (pintype "passive"))
      (node (ref "C22") (pin "1") (pinfunction "1_1") (pintype "passive"))
      (node (ref "C23") (pin "1") (pinfunction "1_1") (pintype "passive"))
      (node (ref "C24") (pin "1") (pinfunction "1_1") (pintype "passive"))
      (node (ref "C25") (pin "1") (pinfunction "1_1") (pintype "passive"))
      (node (ref "C26") (pin "1") (pinfunction "1_1") (pintype "passive"))
      (node (ref "C27") (pin "1") (pinfunction "1_1") (pintype "passive"))
      (node (ref "C28") (pin "1") (pinfunction "1_1") (pintype "passive"))
      (node (ref "C29") (pin "1") (pinfunction "1_1") (pintype "passive"))
      (node (ref "C3") (pin "1") (pinfunction "1_1") (pintype "passive"))
      (node (ref "C4") (pin "1") (pinfunction "1_1") (pintype "passive"))
      (node (ref "C5") (pin "1") (pinfunction "1_1") (pintype "passive"))
      (node (ref "C6") (pin "1") (pinfunction "1_1") (pintype "passive"))
      (node (ref "C7") (pin "2") (pinfunction "2_2") (pintype "passive"))
      (node (ref "C8") (pin "2") (pinfunction "2_2") (pintype "passive"))
      (node (ref "C9") (pin "1") (pinfunction "1_1") (pintype "passive"))
      (node (ref "ECSE2") (pin "5") (pinfunction "5_5") (pintype "passive"))
      (node (ref "ECSE3") (pin "5") (pinfunction "5_5") (pintype "passive"))
      (node (ref "ESC1") (pin "5") (pinfunction "5_5") (pintype "passive"))
      (node (ref "HALL1") (pin "2") (pinfunction "2_2") (pintype "passive"))
      (node (ref "HALL2") (pin "2") (pinfunction "2_2") (pintype "passive"))
      (node (ref "Hall3") (pin "2") (pinfunction "2_2") (pintype "passive"))
      (node (ref "LSConnector") (pin "1") (pinfunction "1_1") (pintype "passive"))
      (node (ref "LSConnector") (pin "3") (pinfunction "3_3") (pintype "passive"))
      (node (ref "LSConnector") (pin "5") (pinfunction "5_5") (pintype "passive"))
      (node (ref "LSConnector") (pin "7") (pinfunction "7_7") (pintype "passive"))
      (node (ref "LineDriver1") (pin "4") (pinfunction "GND_4") (pintype "power_in"))
      (node (ref "LineDriver2") (pin "4") (pinfunction "GND_4") (pintype "power_in"))
      (node (ref "LineDriver3") (pin "4") (pinfunction "GND_4") (pintype "power_in"))
      (node (ref "P1") (pin "1") (pinfunction "1_1") (pintype "passive"))
      (node (ref "R1") (pin "1") (pinfunction "1_1") (pintype "passive"))
      (node (ref "SSR") (pin "2") (pinfunction "-CONTROL_2") (pintype "passive"))
      (node (ref "TransConn1") (pin "6") (pinfunction "6_6") (pintype "passive"))
      (node (ref "TransConn2") (pin "6") (pinfunction "6_6") (pintype "passive"))
      (node (ref "TransConn3") (pin "6") (pinfunction "6_6") (pintype "passive"))
      (node (ref "U1") (pin "2") (pinfunction "GND_2") (pintype "power_in"))
      (node (ref "U1") (pin "4") (pinfunction "GND_4") (pintype "power_in"))
      (node (ref "U2") (pin "12") (pinfunction "GND_12") (pintype "power_in"))
      (node (ref "U2") (pin "27") (pinfunction "GND_27") (pintype "power_in"))
      (node (ref "U2") (pin "3") (pinfunction "GNDA_3") (pintype "power_in"))
      (node (ref "U2") (pin "32") (pinfunction "WAKE_32") (pintype "input"))
      (node (ref "U2") (pin "34") (pinfunction "XOSC0_34") (pintype "input"))
      (node (ref "U2") (pin "35") (pinfunction "GNDX_35") (pintype "power_in"))
      (node (ref "U2") (pin "39") (pinfunction "GND_39") (pintype "power_in"))
      (node (ref "U2") (pin "55") (pinfunction "GND_55") (pintype "power_in"))
      (node (ref "U3") (pin "13") (pinfunction "GND_13") (pintype "passive"))
      (node (ref "U3") (pin "17") (pinfunction "GND_17") (pintype "passive"))
      (node (ref "U3") (pin "3") (pinfunction "GND_3") (pintype "passive"))
      (node (ref "USB1") (pin "4") (pinfunction "GND_4") (pintype "power_in"))
      (node (ref "X1") (pin "2") (pinfunction "CASE_2") (pintype "passive"))
      (node (ref "X1") (pin "4") (pinfunction "CASE_4") (pintype "passive"))
    )
    (net (code "69") (name "Net-(D1-A)") (class "Default")
      (node (ref "D1") (pin "1") (pinfunction "A_1") (pintype "passive"))
      (node (ref "R13") (pin "1") (pinfunction "1_1") (pintype "passive"))
    )
    (net (code "70") (name "Net-(D2-A)") (class "Default")
      (node (ref "D2") (pin "1") (pinfunction "A_1") (pintype "passive"))
      (node (ref "R14") (pin "1") (pinfunction "1_1") (pintype "passive"))
    )
    (net (code "71") (name "Net-(U3-CTS#)") (class "Default")
      (node (ref "R7") (pin "1") (pinfunction "1_1") (pintype "passive"))
      (node (ref "U3") (pin "4") (pinfunction "CTS#_4") (pintype "passive"))
    )
    (net (code "72") (name "Net-(U3-RTS#)") (class "Default")
      (node (ref "R6") (pin "1") (pinfunction "1_1") (pintype "passive"))
      (node (ref "U3") (pin "16") (pinfunction "RTS#_16") (pintype "passive"))
    )
    (net (code "73") (name "Net-(U3-USBDM)") (class "Default")
      (node (ref "R8") (pin "2") (pinfunction "2_2") (pintype "passive"))
      (node (ref "U3") (pin "7") (pinfunction "USBDM_7") (pintype "passive"))
    )
    (net (code "74") (name "Net-(U3-USBDP)") (class "Default")
      (node (ref "R9") (pin "2") (pinfunction "2_2") (pintype "passive"))
      (node (ref "U3") (pin "6") (pinfunction "USBDP_6") (pintype "passive"))
    )
    (net (code "75") (name "VBUS") (class "Default")
      (node (ref "C1") (pin "1") (pinfunction "1_1") (pintype "passive"))
      (node (ref "C3") (pin "2") (pinfunction "2_2") (pintype "passive"))
      (node (ref "L1") (pin "1") (pinfunction "1_1") (pintype "passive"))
      (node (ref "USB1") (pin "1") (pinfunction "VDD_1") (pintype "power_in"))
    )
    (net (code "76") (name "unconnected-(BrConn-Pad2)") (class "Default")
      (node (ref "BrConn") (pin "2") (pinfunction "2_2") (pintype "passive"))
    )
    (net (code "77") (name "unconnected-(ECSE2-Pad7)") (class "Default")
      (node (ref "ECSE2") (pin "7") (pinfunction "7_7") (pintype "passive"))
    )
    (net (code "78") (name "unconnected-(ECSE3-Pad7)") (class "Default")
      (node (ref "ECSE3") (pin "7") (pinfunction "7_7") (pintype "passive"))
    )
    (net (code "79") (name "unconnected-(ESC1-Pad7)") (class "Default")
      (node (ref "ESC1") (pin "7") (pinfunction "7_7") (pintype "passive"))
    )
    (net (code "80") (name "unconnected-(HALL1-Pad6)") (class "Default")
      (node (ref "HALL1") (pin "6") (pinfunction "6_6") (pintype "passive"))
    )
    (net (code "81") (name "unconnected-(HALL2-Pad6)") (class "Default")
      (node (ref "HALL2") (pin "6") (pinfunction "6_6") (pintype "passive"))
    )
    (net (code "82") (name "unconnected-(Hall3-Pad6)") (class "Default")
      (node (ref "Hall3") (pin "6") (pinfunction "6_6") (pintype "passive"))
    )
    (net (code "83") (name "unconnected-(U2-HIB-Pad33)") (class "Default")
      (node (ref "U2") (pin "33") (pinfunction "HIB_33") (pintype "output+no_connect"))
    )
    (net (code "84") (name "unconnected-(U2-PA4{slash}SSI0RX-Pad21)") (class "Default")
      (node (ref "U2") (pin "21") (pinfunction "PA4/SSI0RX_21") (pintype "bidirectional"))
    )
    (net (code "85") (name "unconnected-(U2-PB0{slash}USB0ID-Pad45)") (class "Default")
      (node (ref "U2") (pin "45") (pinfunction "PB0/USB0ID_45") (pintype "bidirectional"))
    )
    (net (code "86") (name "unconnected-(U2-PB1{slash}USB0VBUS-Pad46)") (class "Default")
      (node (ref "U2") (pin "46") (pinfunction "PB1/USB0VBUS_46") (pintype "bidirectional"))
    )
    (net (code "87") (name "unconnected-(U2-PB2{slash}I2COSCL-Pad47)") (class "Default")
      (node (ref "U2") (pin "47") (pinfunction "PB2/I2COSCL_47") (pintype "bidirectional"))
    )
    (net (code "88") (name "unconnected-(U2-PF4-Pad5)") (class "Default")
      (node (ref "U2") (pin "5") (pinfunction "PF4_5") (pintype "bidirectional"))
    )
    (net (code "89") (name "unconnected-(U2-XOSC1-Pad36)") (class "Default")
      (node (ref "U2") (pin "36") (pinfunction "XOSC1_36") (pintype "output+no_connect"))
    )
    (net (code "90") (name "unconnected-(U3-CBUS0-Pad12)") (class "Default")
      (node (ref "U3") (pin "12") (pinfunction "CBUS0_12") (pintype "passive+no_connect"))
    )
    (net (code "91") (name "unconnected-(U3-CBUS3-Pad14)") (class "Default")
      (node (ref "U3") (pin "14") (pinfunction "CBUS3_14") (pintype "passive+no_connect"))
    )
  )
)
